# Pwdr-Circuit-0_1_mk1.net
KiCad netlist of a schematic drawn in EAGLE
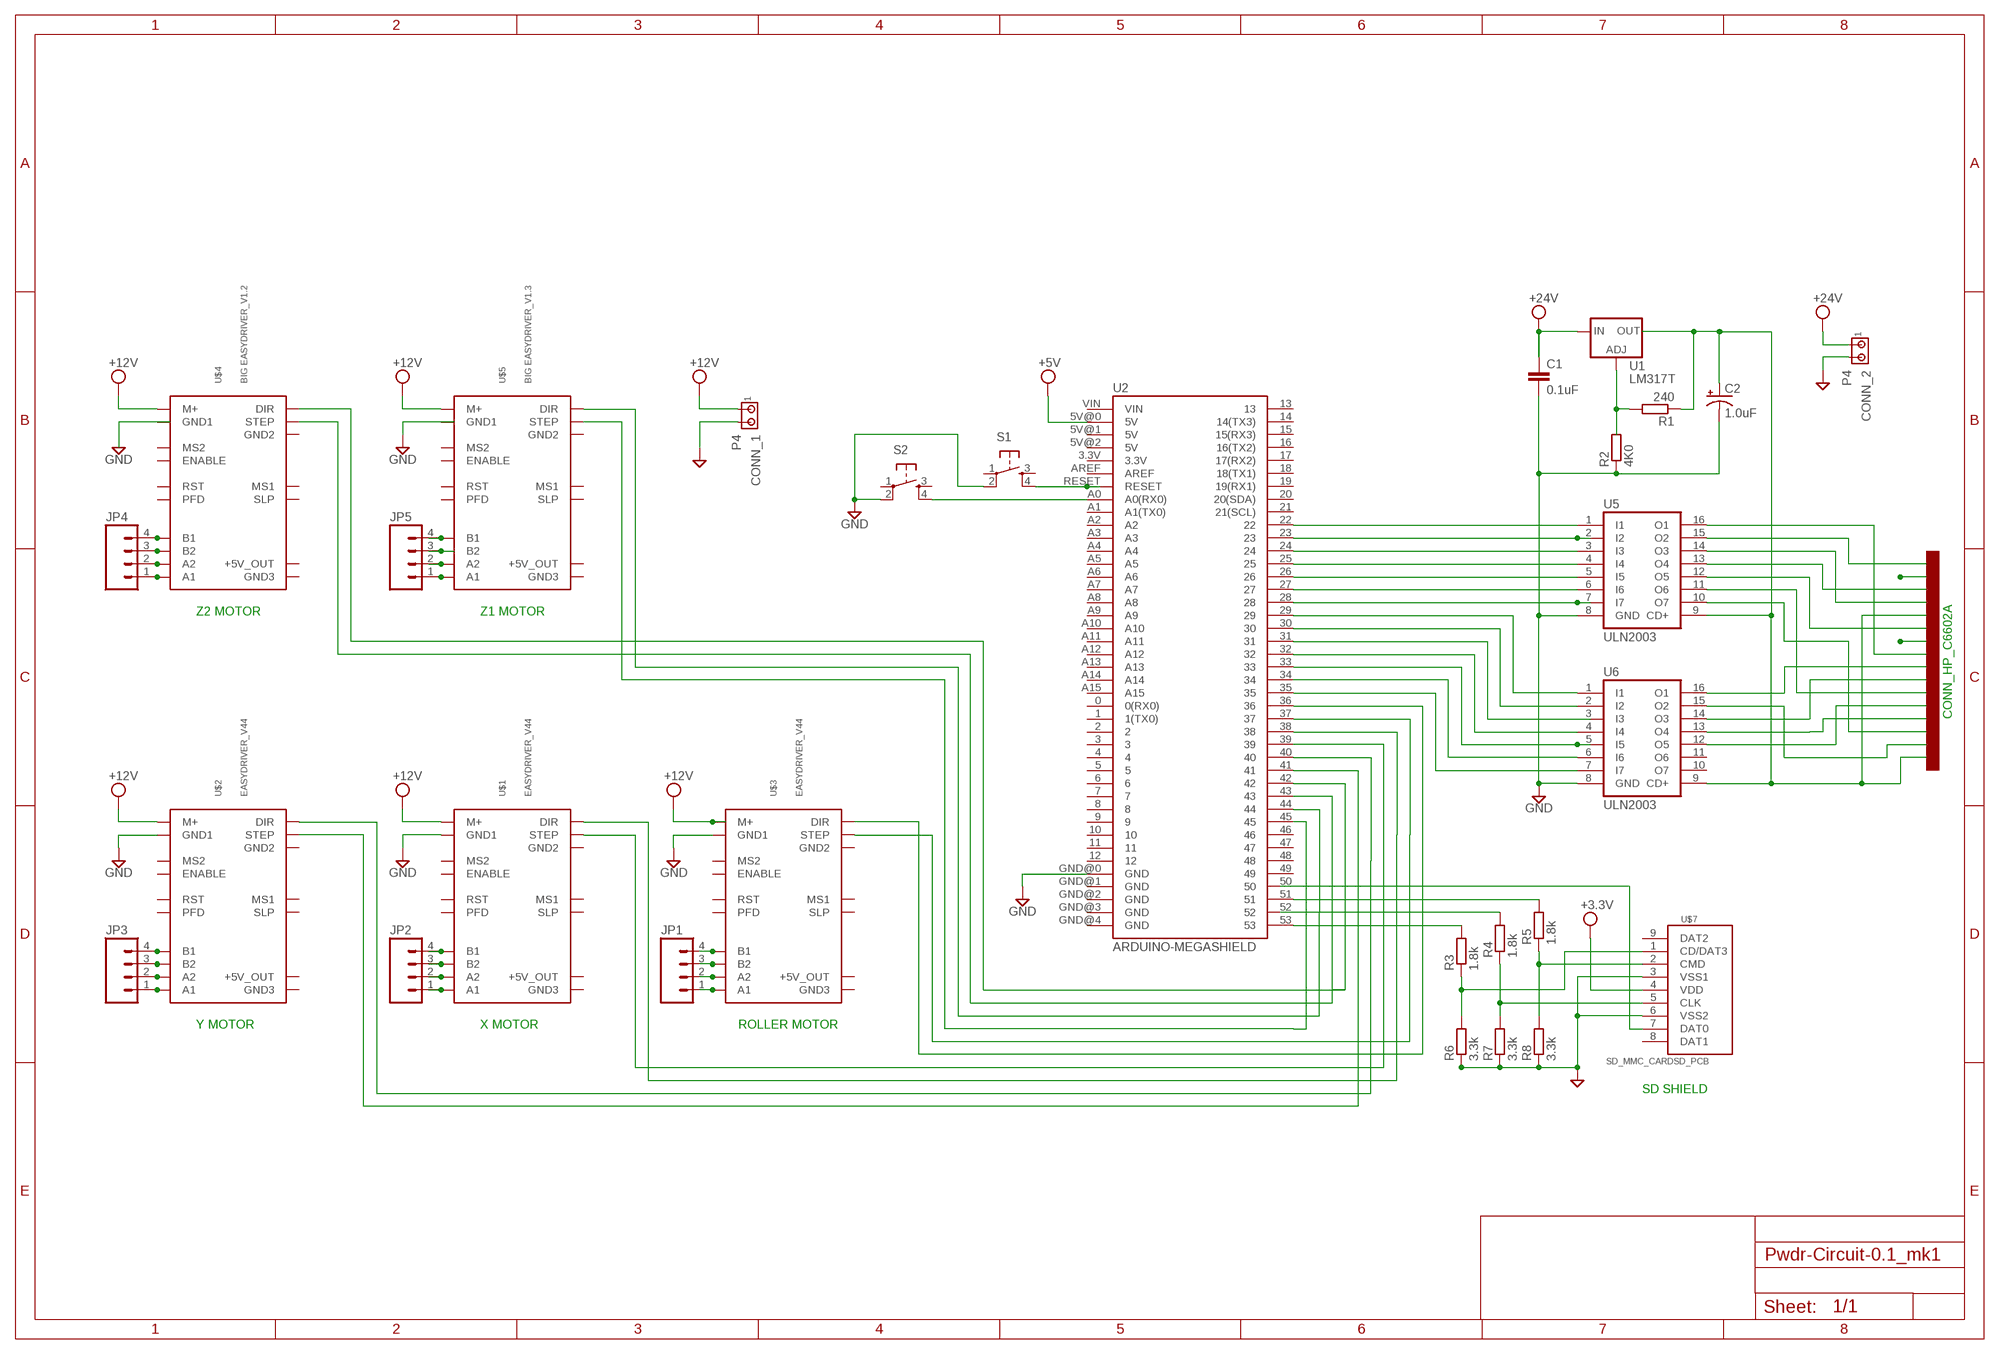
[diagram p0: schematic, sheet 1]

(export (version "E")
  (design (tool "Eeschema 10.0.6"))
  (components
    (comp (ref "C1")
      (value "0.1uF")
      (footprint "eagle-import:C025-024X044")
      (libsource (lib "eagle-import") (part "C-EU025-024X044"))
    )
    (comp (ref "C2")
      (value "1.0uF")
      (footprint "eagle-import:085CS_1AR")
      (libsource (lib "eagle-import") (part "CPOL-US085CS-1AR"))
    )
    (comp (ref "CONN_1")
      (value "P4")
      (footprint "eagle-import:1X2MTA")
      (libsource (lib "eagle-import") (part "MTA02-156"))
    )
    (comp (ref "CONN_2")
      (value "P4")
      (footprint "eagle-import:1X2MTA")
      (libsource (lib "eagle-import") (part "MTA02-156"))
    )
    (comp (ref "JP1")
      (value "M041X04_NO_SILK")
      (footprint "eagle-import:1X04_NO_SILK")
      (libsource (lib "eagle-import") (part "M041X04_NO_SILK"))
    )
    (comp (ref "JP2")
      (value "M041X04_NO_SILK")
      (footprint "eagle-import:1X04_NO_SILK")
      (libsource (lib "eagle-import") (part "M041X04_NO_SILK"))
    )
    (comp (ref "JP3")
      (value "M041X04_NO_SILK")
      (footprint "eagle-import:1X04_NO_SILK")
      (libsource (lib "eagle-import") (part "M041X04_NO_SILK"))
    )
    (comp (ref "JP4")
      (value "M041X04_NO_SILK")
      (footprint "eagle-import:1X04_NO_SILK")
      (libsource (lib "eagle-import") (part "M041X04_NO_SILK"))
    )
    (comp (ref "JP5")
      (value "M041X04_NO_SILK")
      (footprint "eagle-import:1X04_NO_SILK")
      (libsource (lib "eagle-import") (part "M041X04_NO_SILK"))
    )
    (comp (ref "R1")
      (value "240")
      (footprint "eagle-import:0204V")
      (libsource (lib "eagle-import") (part "R-EU_0204/2V"))
    )
    (comp (ref "R2")
      (value "4K0")
      (footprint "eagle-import:0204V")
      (libsource (lib "eagle-import") (part "R-EU_0204/2V"))
    )
    (comp (ref "R3")
      (value "1.8k")
      (footprint "eagle-import:0204V")
      (libsource (lib "eagle-import") (part "R-EU_0204/2V"))
    )
    (comp (ref "R4")
      (value "1.8k")
      (footprint "eagle-import:0204V")
      (libsource (lib "eagle-import") (part "R-EU_0204/2V"))
    )
    (comp (ref "R5")
      (value "1.8k")
      (footprint "eagle-import:0204V")
      (libsource (lib "eagle-import") (part "R-EU_0204/2V"))
    )
    (comp (ref "R6")
      (value "3.3k")
      (footprint "eagle-import:0204V")
      (libsource (lib "eagle-import") (part "R-EU_0204/2V"))
    )
    (comp (ref "R7")
      (value "3.3k")
      (footprint "eagle-import:0204V")
      (libsource (lib "eagle-import") (part "R-EU_0204/2V"))
    )
    (comp (ref "R8")
      (value "3.3k")
      (footprint "eagle-import:0204V")
      (libsource (lib "eagle-import") (part "R-EU_0204/2V"))
    )
    (comp (ref "S1")
      (value "TAC_SWITCHSMD")
      (footprint "eagle-import:TACTILE_SWITCH_SMD")
      (libsource (lib "eagle-import") (part "TAC_SWITCHSMD"))
    )
    (comp (ref "S2")
      (value "TAC_SWITCHSMD")
      (footprint "eagle-import:TACTILE_SWITCH_SMD")
      (libsource (lib "eagle-import") (part "TAC_SWITCHSMD"))
    )
    (comp (ref "U$1")
      (value "EASYDRIVER_V44")
      (footprint "eagle-import:EASYDRIVER_V44")
      (libsource (lib "eagle-import") (part "EASYDRIVER_V44"))
    )
    (comp (ref "U$2")
      (value "EASYDRIVER_V44")
      (footprint "eagle-import:EASYDRIVER_V44")
      (libsource (lib "eagle-import") (part "EASYDRIVER_V44"))
    )
    (comp (ref "U$3")
      (value "EASYDRIVER_V44")
      (footprint "eagle-import:EASYDRIVER_V44")
      (libsource (lib "eagle-import") (part "EASYDRIVER_V44"))
    )
    (comp (ref "U$4")
      (value "BIG EASYDRIVER_V1.2")
      (footprint "eagle-import:EASYDRIVER_V44")
      (libsource (lib "eagle-import") (part "EASYDRIVER_V44"))
    )
    (comp (ref "U$5")
      (value "BIG EASYDRIVER_V1.3")
      (footprint "eagle-import:EASYDRIVER_V44")
      (libsource (lib "eagle-import") (part "EASYDRIVER_V44"))
    )
    (comp (ref "U$7")
      (value "SD_MMC_CARDSD_PCB")
      (footprint "eagle-import:SD-MMC-CARD")
      (libsource (lib "eagle-import") (part "SD_MMC_CARDSD_PCB"))
    )
    (comp (ref "U1")
      (value "LM317T")
      (footprint "eagle-import:317L")
      (libsource (lib "eagle-import") (part "LM317L"))
    )
    (comp (ref "U2")
      (value "ARDUINO-MEGASHIELD")
      (footprint "eagle-import:ARDUINO_MEGA")
      (libsource (lib "eagle-import") (part "ARDUINO-MEGAFULL"))
    )
    (comp (ref "U5")
      (value "ULN2003")
      (footprint "eagle-import:DIL16")
      (libsource (lib "eagle-import") (part "ULN2003AN"))
    )
    (comp (ref "U6")
      (value "ULN2003")
      (footprint "eagle-import:DIL16")
      (libsource (lib "eagle-import") (part "ULN2003AN"))
    )
  )
  (nets
    (net (code "1") (name "+12V") (class "Default")
      (node (ref "C1") (pin "1") (pinfunction "1_1") (pintype "passive"))
      (node (ref "CONN_1") (pin "1") (pinfunction "1_1") (pintype "passive"))
      (node (ref "CONN_2") (pin "1") (pinfunction "1_1") (pintype "passive"))
      (node (ref "U$1") (pin "M+") (pinfunction "M+_M+") (pintype "bidirectional"))
      (node (ref "U$2") (pin "M+") (pinfunction "M+_M+") (pintype "bidirectional"))
      (node (ref "U$3") (pin "M+") (pinfunction "M+_M+") (pintype "bidirectional"))
      (node (ref "U$4") (pin "M+") (pinfunction "M+_M+") (pintype "bidirectional"))
      (node (ref "U$5") (pin "M+") (pinfunction "M+_M+") (pintype "bidirectional"))
      (node (ref "U$7") (pin "4") (pinfunction "VDD_4") (pintype "bidirectional"))
      (node (ref "U1") (pin "3") (pinfunction "IN_3") (pintype "input"))
      (node (ref "U2") (pin "5V@0") (pinfunction "5V_5V@0") (pintype "bidirectional"))
    )
    (net (code "2") (name "AGND") (class "Default")
      (node (ref "C1") (pin "2") (pinfunction "2_2") (pintype "passive"))
      (node (ref "C2") (pin "-") (pinfunction "-_-") (pintype "passive"))
      (node (ref "CONN_1") (pin "2") (pinfunction "2_2") (pintype "passive"))
      (node (ref "CONN_2") (pin "2") (pinfunction "2_2") (pintype "passive"))
      (node (ref "R2") (pin "1") (pinfunction "1_1") (pintype "passive"))
      (node (ref "R6") (pin "1") (pinfunction "1_1") (pintype "passive"))
      (node (ref "R7") (pin "1") (pinfunction "1_1") (pintype "passive"))
      (node (ref "R8") (pin "1") (pinfunction "1_1") (pintype "passive"))
      (node (ref "S1") (pin "2") (pinfunction "2_2") (pintype "passive"))
      (node (ref "S2") (pin "2") (pinfunction "2_2") (pintype "passive"))
      (node (ref "U$1") (pin "GND1") (pinfunction "GND1_GND1") (pintype "bidirectional"))
      (node (ref "U$2") (pin "GND1") (pinfunction "GND1_GND1") (pintype "bidirectional"))
      (node (ref "U$3") (pin "GND1") (pinfunction "GND1_GND1") (pintype "bidirectional"))
      (node (ref "U$4") (pin "GND1") (pinfunction "GND1_GND1") (pintype "bidirectional"))
      (node (ref "U$5") (pin "GND1") (pinfunction "GND1_GND1") (pintype "bidirectional"))
      (node (ref "U$7") (pin "3") (pinfunction "VSS1_3") (pintype "bidirectional"))
      (node (ref "U$7") (pin "6") (pinfunction "VSS2_6") (pintype "bidirectional"))
      (node (ref "U2") (pin "GND@0") (pinfunction "GND_GND@0") (pintype "bidirectional"))
      (node (ref "U5") (pin "8") (pinfunction "GND_8") (pintype "power_in"))
      (node (ref "U6") (pin "8") (pinfunction "GND_8") (pintype "power_in"))
    )
    (net (code "3") (name "Net-(JP1-Pad1)") (class "Default")
      (node (ref "JP1") (pin "1") (pinfunction "1_1") (pintype "passive"))
      (node (ref "U$3") (pin "A1") (pinfunction "A1_A1") (pintype "bidirectional"))
    )
    (net (code "4") (name "Net-(JP1-Pad2)") (class "Default")
      (node (ref "JP1") (pin "2") (pinfunction "2_2") (pintype "passive"))
      (node (ref "U$3") (pin "A2") (pinfunction "A2_A2") (pintype "bidirectional"))
    )
    (net (code "5") (name "Net-(JP1-Pad3)") (class "Default")
      (node (ref "JP1") (pin "3") (pinfunction "3_3") (pintype "passive"))
      (node (ref "U$3") (pin "B2") (pinfunction "B2_B2") (pintype "bidirectional"))
    )
    (net (code "6") (name "Net-(JP1-Pad4)") (class "Default")
      (node (ref "JP1") (pin "4") (pinfunction "4_4") (pintype "passive"))
      (node (ref "U$3") (pin "B1") (pinfunction "B1_B1") (pintype "bidirectional"))
    )
    (net (code "7") (name "Net-(JP2-Pad1)") (class "Default")
      (node (ref "JP2") (pin "1") (pinfunction "1_1") (pintype "passive"))
      (node (ref "U$1") (pin "A1") (pinfunction "A1_A1") (pintype "bidirectional"))
    )
    (net (code "8") (name "Net-(JP2-Pad2)") (class "Default")
      (node (ref "JP2") (pin "2") (pinfunction "2_2") (pintype "passive"))
      (node (ref "U$1") (pin "A2") (pinfunction "A2_A2") (pintype "bidirectional"))
    )
    (net (code "9") (name "Net-(JP2-Pad3)") (class "Default")
      (node (ref "JP2") (pin "3") (pinfunction "3_3") (pintype "passive"))
      (node (ref "U$1") (pin "B2") (pinfunction "B2_B2") (pintype "bidirectional"))
    )
    (net (code "10") (name "Net-(JP2-Pad4)") (class "Default")
      (node (ref "JP2") (pin "4") (pinfunction "4_4") (pintype "passive"))
      (node (ref "U$1") (pin "B1") (pinfunction "B1_B1") (pintype "bidirectional"))
    )
    (net (code "11") (name "Net-(JP3-Pad1)") (class "Default")
      (node (ref "JP3") (pin "1") (pinfunction "1_1") (pintype "passive"))
      (node (ref "U$2") (pin "A1") (pinfunction "A1_A1") (pintype "bidirectional"))
    )
    (net (code "12") (name "Net-(JP3-Pad2)") (class "Default")
      (node (ref "JP3") (pin "2") (pinfunction "2_2") (pintype "passive"))
      (node (ref "U$2") (pin "A2") (pinfunction "A2_A2") (pintype "bidirectional"))
    )
    (net (code "13") (name "Net-(JP3-Pad3)") (class "Default")
      (node (ref "JP3") (pin "3") (pinfunction "3_3") (pintype "passive"))
      (node (ref "U$2") (pin "B2") (pinfunction "B2_B2") (pintype "bidirectional"))
    )
    (net (code "14") (name "Net-(JP3-Pad4)") (class "Default")
      (node (ref "JP3") (pin "4") (pinfunction "4_4") (pintype "passive"))
      (node (ref "U$2") (pin "B1") (pinfunction "B1_B1") (pintype "bidirectional"))
    )
    (net (code "15") (name "Net-(JP4-Pad1)") (class "Default")
      (node (ref "JP4") (pin "1") (pinfunction "1_1") (pintype "passive"))
      (node (ref "U$4") (pin "A1") (pinfunction "A1_A1") (pintype "bidirectional"))
    )
    (net (code "16") (name "Net-(JP4-Pad2)") (class "Default")
      (node (ref "JP4") (pin "2") (pinfunction "2_2") (pintype "passive"))
      (node (ref "U$4") (pin "A2") (pinfunction "A2_A2") (pintype "bidirectional"))
    )
    (net (code "17") (name "Net-(JP4-Pad3)") (class "Default")
      (node (ref "JP4") (pin "3") (pinfunction "3_3") (pintype "passive"))
      (node (ref "U$4") (pin "B2") (pinfunction "B2_B2") (pintype "bidirectional"))
    )
    (net (code "18") (name "Net-(JP4-Pad4)") (class "Default")
      (node (ref "JP4") (pin "4") (pinfunction "4_4") (pintype "passive"))
      (node (ref "U$4") (pin "B1") (pinfunction "B1_B1") (pintype "bidirectional"))
    )
    (net (code "19") (name "Net-(JP5-Pad1)") (class "Default")
      (node (ref "JP5") (pin "1") (pinfunction "1_1") (pintype "passive"))
      (node (ref "U$5") (pin "A1") (pinfunction "A1_A1") (pintype "bidirectional"))
    )
    (net (code "20") (name "Net-(JP5-Pad2)") (class "Default")
      (node (ref "JP5") (pin "2") (pinfunction "2_2") (pintype "passive"))
      (node (ref "U$5") (pin "A2") (pinfunction "A2_A2") (pintype "bidirectional"))
    )
    (net (code "21") (name "Net-(JP5-Pad3)") (class "Default")
      (node (ref "JP5") (pin "3") (pinfunction "3_3") (pintype "passive"))
      (node (ref "U$5") (pin "B2") (pinfunction "B2_B2") (pintype "bidirectional"))
    )
    (net (code "22") (name "Net-(JP5-Pad4)") (class "Default")
      (node (ref "JP5") (pin "4") (pinfunction "4_4") (pintype "passive"))
      (node (ref "U$5") (pin "B1") (pinfunction "B1_B1") (pintype "bidirectional"))
    )
    (net (code "23") (name "Net-(R3-Pad2)") (class "Default")
      (node (ref "R3") (pin "2") (pinfunction "2_2") (pintype "passive"))
      (node (ref "U2") (pin "53") (pinfunction "53_53") (pintype "bidirectional"))
    )
    (net (code "24") (name "Net-(R5-Pad2)") (class "Default")
      (node (ref "R5") (pin "2") (pinfunction "2_2") (pintype "passive"))
      (node (ref "U2") (pin "51") (pinfunction "51_51") (pintype "bidirectional"))
    )
    (net (code "25") (name "Net-(S1-Pad4)") (class "Default")
      (node (ref "S1") (pin "4") (pinfunction "4_4") (pintype "passive"))
      (node (ref "U2") (pin "RESET") (pinfunction "RESET_RESET") (pintype "bidirectional"))
    )
    (net (code "26") (name "Net-(U$1-PadDIR)") (class "Default")
      (node (ref "U$1") (pin "DIR") (pinfunction "DIR_DIR") (pintype "bidirectional"))
      (node (ref "U$2") (pin "DIR") (pinfunction "DIR_DIR") (pintype "bidirectional"))
      (node (ref "U2") (pin "38") (pinfunction "38_38") (pintype "bidirectional"))
      (node (ref "U2") (pin "40") (pinfunction "40_40") (pintype "bidirectional"))
    )
    (net (code "27") (name "Net-(U$1-PadSTEP)") (class "Default")
      (node (ref "U$1") (pin "STEP") (pinfunction "STEP_STEP") (pintype "bidirectional"))
      (node (ref "U2") (pin "39") (pinfunction "39_39") (pintype "bidirectional"))
    )
    (net (code "28") (name "Net-(U$2-PadSTEP)") (class "Default")
      (node (ref "U$2") (pin "STEP") (pinfunction "STEP_STEP") (pintype "bidirectional"))
      (node (ref "U2") (pin "41") (pinfunction "41_41") (pintype "bidirectional"))
    )
    (net (code "29") (name "Net-(U$3-PadDIR)") (class "Default")
      (node (ref "U$3") (pin "DIR") (pinfunction "DIR_DIR") (pintype "bidirectional"))
      (node (ref "U2") (pin "36") (pinfunction "36_36") (pintype "bidirectional"))
    )
    (net (code "30") (name "Net-(U$3-PadSTEP)") (class "Default")
      (node (ref "U$3") (pin "STEP") (pinfunction "STEP_STEP") (pintype "bidirectional"))
      (node (ref "U2") (pin "37") (pinfunction "37_37") (pintype "bidirectional"))
    )
    (net (code "31") (name "Net-(U$4-PadDIR)") (class "Default")
      (node (ref "U$4") (pin "DIR") (pinfunction "DIR_DIR") (pintype "bidirectional"))
      (node (ref "U2") (pin "42") (pinfunction "42_42") (pintype "bidirectional"))
    )
    (net (code "32") (name "Net-(U$4-PadSTEP)") (class "Default")
      (node (ref "U$4") (pin "STEP") (pinfunction "STEP_STEP") (pintype "bidirectional"))
      (node (ref "U2") (pin "43") (pinfunction "43_43") (pintype "bidirectional"))
    )
    (net (code "33") (name "Net-(U$5-PadDIR)") (class "Default")
      (node (ref "U$5") (pin "DIR") (pinfunction "DIR_DIR") (pintype "bidirectional"))
      (node (ref "U2") (pin "44") (pinfunction "44_44") (pintype "bidirectional"))
    )
    (net (code "34") (name "Net-(U$5-PadSTEP)") (class "Default")
      (node (ref "U$5") (pin "STEP") (pinfunction "STEP_STEP") (pintype "bidirectional"))
      (node (ref "U2") (pin "45") (pinfunction "45_45") (pintype "bidirectional"))
    )
    (net (code "35") (name "Net-(U$7-CD{slash}DAT3)") (class "Default")
      (node (ref "R3") (pin "1") (pinfunction "1_1") (pintype "passive"))
      (node (ref "R6") (pin "2") (pinfunction "2_2") (pintype "passive"))
      (node (ref "U$7") (pin "1") (pinfunction "CD/DAT3_1") (pintype "bidirectional"))
    )
    (net (code "36") (name "Net-(U$7-CLK)") (class "Default")
      (node (ref "R4") (pin "1") (pinfunction "1_1") (pintype "passive"))
      (node (ref "R7") (pin "2") (pinfunction "2_2") (pintype "passive"))
      (node (ref "U$7") (pin "5") (pinfunction "CLK_5") (pintype "bidirectional"))
    )
    (net (code "37") (name "Net-(U$7-CMD)") (class "Default")
      (node (ref "R5") (pin "1") (pinfunction "1_1") (pintype "passive"))
      (node (ref "R8") (pin "2") (pinfunction "2_2") (pintype "passive"))
      (node (ref "U$7") (pin "2") (pinfunction "CMD_2") (pintype "bidirectional"))
    )
    (net (code "38") (name "Net-(U1-ADJ)") (class "Default")
      (node (ref "R1") (pin "2") (pinfunction "2_2") (pintype "passive"))
      (node (ref "R2") (pin "2") (pinfunction "2_2") (pintype "passive"))
      (node (ref "U1") (pin "1") (pinfunction "ADJ_1") (pintype "input"))
    )
    (net (code "39") (name "Net-(U1-OUT)") (class "Default")
      (node (ref "C2") (pin "+") (pinfunction "+_+") (pintype "passive"))
      (node (ref "R1") (pin "1") (pinfunction "1_1") (pintype "passive"))
      (node (ref "U1") (pin "2") (pinfunction "OUT_2") (pintype "passive"))
      (node (ref "U5") (pin "9") (pinfunction "CD+_9") (pintype "passive"))
      (node (ref "U6") (pin "9") (pinfunction "CD+_9") (pintype "passive"))
    )
    (net (code "40") (name "Net-(U2-A0(RX0))") (class "Default")
      (node (ref "S2") (pin "4") (pinfunction "4_4") (pintype "passive"))
      (node (ref "U2") (pin "A0") (pinfunction "A0(RX0)_A0") (pintype "bidirectional"))
    )
    (net (code "41") (name "Net-(U5-I1)") (class "Default")
      (node (ref "U2") (pin "22") (pinfunction "22_22") (pintype "bidirectional"))
      (node (ref "U5") (pin "1") (pinfunction "I1_1") (pintype "input"))
    )
    (net (code "42") (name "Net-(U5-I2)") (class "Default")
      (node (ref "U2") (pin "23") (pinfunction "23_23") (pintype "bidirectional"))
      (node (ref "U5") (pin "2") (pinfunction "I2_2") (pintype "input"))
    )
    (net (code "43") (name "Net-(U5-I3)") (class "Default")
      (node (ref "U2") (pin "24") (pinfunction "24_24") (pintype "bidirectional"))
      (node (ref "U5") (pin "3") (pinfunction "I3_3") (pintype "input"))
    )
    (net (code "44") (name "Net-(U5-I4)") (class "Default")
      (node (ref "U2") (pin "25") (pinfunction "25_25") (pintype "bidirectional"))
      (node (ref "U5") (pin "4") (pinfunction "I4_4") (pintype "input"))
    )
    (net (code "45") (name "Net-(U5-I5)") (class "Default")
      (node (ref "U2") (pin "26") (pinfunction "26_26") (pintype "bidirectional"))
      (node (ref "U5") (pin "5") (pinfunction "I5_5") (pintype "input"))
    )
    (net (code "46") (name "Net-(U5-I6)") (class "Default")
      (node (ref "U2") (pin "27") (pinfunction "27_27") (pintype "bidirectional"))
      (node (ref "U5") (pin "6") (pinfunction "I6_6") (pintype "input"))
    )
    (net (code "47") (name "Net-(U5-I7)") (class "Default")
      (node (ref "U2") (pin "28") (pinfunction "28_28") (pintype "bidirectional"))
      (node (ref "U5") (pin "7") (pinfunction "I7_7") (pintype "input"))
    )
    (net (code "48") (name "Net-(U6-I1)") (class "Default")
      (node (ref "U2") (pin "29") (pinfunction "29_29") (pintype "bidirectional"))
      (node (ref "U6") (pin "1") (pinfunction "I1_1") (pintype "input"))
    )
    (net (code "49") (name "Net-(U6-I2)") (class "Default")
      (node (ref "U2") (pin "30") (pinfunction "30_30") (pintype "bidirectional"))
      (node (ref "U6") (pin "2") (pinfunction "I2_2") (pintype "input"))
    )
    (net (code "50") (name "Net-(U6-I3)") (class "Default")
      (node (ref "U2") (pin "31") (pinfunction "31_31") (pintype "bidirectional"))
      (node (ref "U6") (pin "3") (pinfunction "I3_3") (pintype "input"))
    )
    (net (code "51") (name "Net-(U6-I4)") (class "Default")
      (node (ref "U2") (pin "32") (pinfunction "32_32") (pintype "bidirectional"))
      (node (ref "U6") (pin "4") (pinfunction "I4_4") (pintype "input"))
    )
    (net (code "52") (name "Net-(U6-I5)") (class "Default")
      (node (ref "U2") (pin "33") (pinfunction "33_33") (pintype "bidirectional"))
      (node (ref "U6") (pin "5") (pinfunction "I5_5") (pintype "input"))
    )
    (net (code "53") (name "Net-(U6-I6)") (class "Default")
      (node (ref "U2") (pin "34") (pinfunction "34_34") (pintype "bidirectional"))
      (node (ref "U6") (pin "6") (pinfunction "I6_6") (pintype "input"))
    )
    (net (code "54") (name "Net-(U6-I7)") (class "Default")
      (node (ref "U2") (pin "35") (pinfunction "35_35") (pintype "bidirectional"))
      (node (ref "U6") (pin "7") (pinfunction "I7_7") (pintype "input"))
    )
    (net (code "55") (name "unconnected-(R4-Pad2)") (class "Default")
      (node (ref "R4") (pin "2") (pinfunction "2_2") (pintype "passive"))
    )
    (net (code "56") (name "unconnected-(S1-Pad1)") (class "Default")
      (node (ref "S1") (pin "1") (pinfunction "1_1") (pintype "passive"))
    )
    (net (code "57") (name "unconnected-(S1-Pad3)") (class "Default")
      (node (ref "S1") (pin "3") (pinfunction "3_3") (pintype "passive"))
    )
    (net (code "58") (name "unconnected-(S2-Pad1)") (class "Default")
      (node (ref "S2") (pin "1") (pinfunction "1_1") (pintype "passive"))
    )
    (net (code "59") (name "unconnected-(S2-Pad3)") (class "Default")
      (node (ref "S2") (pin "3") (pinfunction "3_3") (pintype "passive"))
    )
    (net (code "60") (name "unconnected-(U$1-+5V_OUT-PadP$11)") (class "Default")
      (node (ref "U$1") (pin "P$11") (pinfunction "+5V_OUT_P$11") (pintype "bidirectional"))
    )
    (net (code "61") (name "unconnected-(U$1-PadENABLE)") (class "Default")
      (node (ref "U$1") (pin "ENABLE") (pinfunction "ENABLE_ENABLE") (pintype "bidirectional"))
    )
    (net (code "62") (name "unconnected-(U$1-PadGND2)") (class "Default")
      (node (ref "U$1") (pin "GND2") (pinfunction "GND2_GND2") (pintype "bidirectional"))
    )
    (net (code "63") (name "unconnected-(U$1-PadGND3)") (class "Default")
      (node (ref "U$1") (pin "GND3") (pinfunction "GND3_GND3") (pintype "bidirectional"))
    )
    (net (code "64") (name "unconnected-(U$1-PadMS1)") (class "Default")
      (node (ref "U$1") (pin "MS1") (pinfunction "MS1_MS1") (pintype "bidirectional"))
    )
    (net (code "65") (name "unconnected-(U$1-PadMS2)") (class "Default")
      (node (ref "U$1") (pin "MS2") (pinfunction "MS2_MS2") (pintype "bidirectional"))
    )
    (net (code "66") (name "unconnected-(U$1-PadPFD)") (class "Default")
      (node (ref "U$1") (pin "PFD") (pinfunction "PFD_PFD") (pintype "bidirectional"))
    )
    (net (code "67") (name "unconnected-(U$1-PadRST)") (class "Default")
      (node (ref "U$1") (pin "RST") (pinfunction "RST_RST") (pintype "bidirectional"))
    )
    (net (code "68") (name "unconnected-(U$1-SLP-PadSLEEP)") (class "Default")
      (node (ref "U$1") (pin "SLEEP") (pinfunction "SLP_SLEEP") (pintype "bidirectional"))
    )
    (net (code "69") (name "unconnected-(U$2-+5V_OUT-PadP$11)") (class "Default")
      (node (ref "U$2") (pin "P$11") (pinfunction "+5V_OUT_P$11") (pintype "bidirectional"))
    )
    (net (code "70") (name "unconnected-(U$2-PadENABLE)") (class "Default")
      (node (ref "U$2") (pin "ENABLE") (pinfunction "ENABLE_ENABLE") (pintype "bidirectional"))
    )
    (net (code "71") (name "unconnected-(U$2-PadGND2)") (class "Default")
      (node (ref "U$2") (pin "GND2") (pinfunction "GND2_GND2") (pintype "bidirectional"))
    )
    (net (code "72") (name "unconnected-(U$2-PadGND3)") (class "Default")
      (node (ref "U$2") (pin "GND3") (pinfunction "GND3_GND3") (pintype "bidirectional"))
    )
    (net (code "73") (name "unconnected-(U$2-PadMS1)") (class "Default")
      (node (ref "U$2") (pin "MS1") (pinfunction "MS1_MS1") (pintype "bidirectional"))
    )
    (net (code "74") (name "unconnected-(U$2-PadMS2)") (class "Default")
      (node (ref "U$2") (pin "MS2") (pinfunction "MS2_MS2") (pintype "bidirectional"))
    )
    (net (code "75") (name "unconnected-(U$2-PadPFD)") (class "Default")
      (node (ref "U$2") (pin "PFD") (pinfunction "PFD_PFD") (pintype "bidirectional"))
    )
    (net (code "76") (name "unconnected-(U$2-PadRST)") (class "Default")
      (node (ref "U$2") (pin "RST") (pinfunction "RST_RST") (pintype "bidirectional"))
    )
    (net (code "77") (name "unconnected-(U$2-SLP-PadSLEEP)") (class "Default")
      (node (ref "U$2") (pin "SLEEP") (pinfunction "SLP_SLEEP") (pintype "bidirectional"))
    )
    (net (code "78") (name "unconnected-(U$3-+5V_OUT-PadP$11)") (class "Default")
      (node (ref "U$3") (pin "P$11") (pinfunction "+5V_OUT_P$11") (pintype "bidirectional"))
    )
    (net (code "79") (name "unconnected-(U$3-PadENABLE)") (class "Default")
      (node (ref "U$3") (pin "ENABLE") (pinfunction "ENABLE_ENABLE") (pintype "bidirectional"))
    )
    (net (code "80") (name "unconnected-(U$3-PadGND2)") (class "Default")
      (node (ref "U$3") (pin "GND2") (pinfunction "GND2_GND2") (pintype "bidirectional"))
    )
    (net (code "81") (name "unconnected-(U$3-PadGND3)") (class "Default")
      (node (ref "U$3") (pin "GND3") (pinfunction "GND3_GND3") (pintype "bidirectional"))
    )
    (net (code "82") (name "unconnected-(U$3-PadMS1)") (class "Default")
      (node (ref "U$3") (pin "MS1") (pinfunction "MS1_MS1") (pintype "bidirectional"))
    )
    (net (code "83") (name "unconnected-(U$3-PadMS2)") (class "Default")
      (node (ref "U$3") (pin "MS2") (pinfunction "MS2_MS2") (pintype "bidirectional"))
    )
    (net (code "84") (name "unconnected-(U$3-PadPFD)") (class "Default")
      (node (ref "U$3") (pin "PFD") (pinfunction "PFD_PFD") (pintype "bidirectional"))
    )
    (net (code "85") (name "unconnected-(U$3-PadRST)") (class "Default")
      (node (ref "U$3") (pin "RST") (pinfunction "RST_RST") (pintype "bidirectional"))
    )
    (net (code "86") (name "unconnected-(U$3-SLP-PadSLEEP)") (class "Default")
      (node (ref "U$3") (pin "SLEEP") (pinfunction "SLP_SLEEP") (pintype "bidirectional"))
    )
    (net (code "87") (name "unconnected-(U$4-+5V_OUT-PadP$11)") (class "Default")
      (node (ref "U$4") (pin "P$11") (pinfunction "+5V_OUT_P$11") (pintype "bidirectional"))
    )
    (net (code "88") (name "unconnected-(U$4-PadENABLE)") (class "Default")
      (node (ref "U$4") (pin "ENABLE") (pinfunction "ENABLE_ENABLE") (pintype "bidirectional"))
    )
    (net (code "89") (name "unconnected-(U$4-PadGND2)") (class "Default")
      (node (ref "U$4") (pin "GND2") (pinfunction "GND2_GND2") (pintype "bidirectional"))
    )
    (net (code "90") (name "unconnected-(U$4-PadGND3)") (class "Default")
      (node (ref "U$4") (pin "GND3") (pinfunction "GND3_GND3") (pintype "bidirectional"))
    )
    (net (code "91") (name "unconnected-(U$4-PadMS1)") (class "Default")
      (node (ref "U$4") (pin "MS1") (pinfunction "MS1_MS1") (pintype "bidirectional"))
    )
    (net (code "92") (name "unconnected-(U$4-PadMS2)") (class "Default")
      (node (ref "U$4") (pin "MS2") (pinfunction "MS2_MS2") (pintype "bidirectional"))
    )
    (net (code "93") (name "unconnected-(U$4-PadPFD)") (class "Default")
      (node (ref "U$4") (pin "PFD") (pinfunction "PFD_PFD") (pintype "bidirectional"))
    )
    (net (code "94") (name "unconnected-(U$4-PadRST)") (class "Default")
      (node (ref "U$4") (pin "RST") (pinfunction "RST_RST") (pintype "bidirectional"))
    )
    (net (code "95") (name "unconnected-(U$4-SLP-PadSLEEP)") (class "Default")
      (node (ref "U$4") (pin "SLEEP") (pinfunction "SLP_SLEEP") (pintype "bidirectional"))
    )
    (net (code "96") (name "unconnected-(U$5-+5V_OUT-PadP$11)") (class "Default")
      (node (ref "U$5") (pin "P$11") (pinfunction "+5V_OUT_P$11") (pintype "bidirectional"))
    )
    (net (code "97") (name "unconnected-(U$5-PadENABLE)") (class "Default")
      (node (ref "U$5") (pin "ENABLE") (pinfunction "ENABLE_ENABLE") (pintype "bidirectional"))
    )
    (net (code "98") (name "unconnected-(U$5-PadGND2)") (class "Default")
      (node (ref "U$5") (pin "GND2") (pinfunction "GND2_GND2") (pintype "bidirectional"))
    )
    (net (code "99") (name "unconnected-(U$5-PadGND3)") (class "Default")
      (node (ref "U$5") (pin "GND3") (pinfunction "GND3_GND3") (pintype "bidirectional"))
    )
    (net (code "100") (name "unconnected-(U$5-PadMS1)") (class "Default")
      (node (ref "U$5") (pin "MS1") (pinfunction "MS1_MS1") (pintype "bidirectional"))
    )
    (net (code "101") (name "unconnected-(U$5-PadMS2)") (class "Default")
      (node (ref "U$5") (pin "MS2") (pinfunction "MS2_MS2") (pintype "bidirectional"))
    )
    (net (code "102") (name "unconnected-(U$5-PadPFD)") (class "Default")
      (node (ref "U$5") (pin "PFD") (pinfunction "PFD_PFD") (pintype "bidirectional"))
    )
    (net (code "103") (name "unconnected-(U$5-PadRST)") (class "Default")
      (node (ref "U$5") (pin "RST") (pinfunction "RST_RST") (pintype "bidirectional"))
    )
    (net (code "104") (name "unconnected-(U$5-SLP-PadSLEEP)") (class "Default")
      (node (ref "U$5") (pin "SLEEP") (pinfunction "SLP_SLEEP") (pintype "bidirectional"))
    )
    (net (code "105") (name "unconnected-(U$7-DAT0-Pad7)") (class "Default")
      (node (ref "U$7") (pin "7") (pinfunction "DAT0_7") (pintype "bidirectional"))
    )
    (net (code "106") (name "unconnected-(U$7-DAT1-Pad8)") (class "Default")
      (node (ref "U$7") (pin "8") (pinfunction "DAT1_8") (pintype "bidirectional"))
    )
    (net (code "107") (name "unconnected-(U$7-DAT2-Pad9)") (class "Default")
      (node (ref "U$7") (pin "9") (pinfunction "DAT2_9") (pintype "bidirectional"))
    )
    (net (code "108") (name "unconnected-(U2-0(RX0)-Pad0)") (class "Default")
      (node (ref "U2") (pin "0") (pinfunction "0(RX0)_0") (pintype "bidirectional"))
    )
    (net (code "109") (name "unconnected-(U2-1(TX0)-Pad1)") (class "Default")
      (node (ref "U2") (pin "1") (pinfunction "1(TX0)_1") (pintype "bidirectional"))
    )
    (net (code "110") (name "unconnected-(U2-5V-Pad5V@1)") (class "Default")
      (node (ref "U2") (pin "5V@1") (pinfunction "5V_5V@1") (pintype "bidirectional"))
    )
    (net (code "111") (name "unconnected-(U2-5V-Pad5V@2)") (class "Default")
      (node (ref "U2") (pin "5V@2") (pinfunction "5V_5V@2") (pintype "bidirectional"))
    )
    (net (code "112") (name "unconnected-(U2-14(TX3)-Pad14)") (class "Default")
      (node (ref "U2") (pin "14") (pinfunction "14(TX3)_14") (pintype "bidirectional"))
    )
    (net (code "113") (name "unconnected-(U2-15(RX3)-Pad15)") (class "Default")
      (node (ref "U2") (pin "15") (pinfunction "15(RX3)_15") (pintype "bidirectional"))
    )
    (net (code "114") (name "unconnected-(U2-16(TX2)-Pad16)") (class "Default")
      (node (ref "U2") (pin "16") (pinfunction "16(TX2)_16") (pintype "bidirectional"))
    )
    (net (code "115") (name "unconnected-(U2-17(RX2)-Pad17)") (class "Default")
      (node (ref "U2") (pin "17") (pinfunction "17(RX2)_17") (pintype "bidirectional"))
    )
    (net (code "116") (name "unconnected-(U2-18(TX1)-Pad18)") (class "Default")
      (node (ref "U2") (pin "18") (pinfunction "18(TX1)_18") (pintype "bidirectional"))
    )
    (net (code "117") (name "unconnected-(U2-19(RX1)-Pad19)") (class "Default")
      (node (ref "U2") (pin "19") (pinfunction "19(RX1)_19") (pintype "bidirectional"))
    )
    (net (code "118") (name "unconnected-(U2-20(SDA)-Pad20)") (class "Default")
      (node (ref "U2") (pin "20") (pinfunction "20(SDA)_20") (pintype "bidirectional"))
    )
    (net (code "119") (name "unconnected-(U2-21(SCL)-Pad21)") (class "Default")
      (node (ref "U2") (pin "21") (pinfunction "21(SCL)_21") (pintype "bidirectional"))
    )
    (net (code "120") (name "unconnected-(U2-A1(TX0)-PadA1)") (class "Default")
      (node (ref "U2") (pin "A1") (pinfunction "A1(TX0)_A1") (pintype "bidirectional"))
    )
    (net (code "121") (name "unconnected-(U2-GND-PadGND@1)") (class "Default")
      (node (ref "U2") (pin "GND@1") (pinfunction "GND_GND@1") (pintype "bidirectional"))
    )
    (net (code "122") (name "unconnected-(U2-GND-PadGND@2)") (class "Default")
      (node (ref "U2") (pin "GND@2") (pinfunction "GND_GND@2") (pintype "bidirectional"))
    )
    (net (code "123") (name "unconnected-(U2-GND-PadGND@3)") (class "Default")
      (node (ref "U2") (pin "GND@3") (pinfunction "GND_GND@3") (pintype "bidirectional"))
    )
    (net (code "124") (name "unconnected-(U2-GND-PadGND@4)") (class "Default")
      (node (ref "U2") (pin "GND@4") (pinfunction "GND_GND@4") (pintype "bidirectional"))
    )
    (net (code "125") (name "unconnected-(U2-Pad2)") (class "Default")
      (node (ref "U2") (pin "2") (pinfunction "2_2") (pintype "bidirectional"))
    )
    (net (code "126") (name "unconnected-(U2-Pad3)") (class "Default")
      (node (ref "U2") (pin "3") (pinfunction "3_3") (pintype "bidirectional"))
    )
    (net (code "127") (name "unconnected-(U2-Pad3.3V)") (class "Default")
      (node (ref "U2") (pin "3.3V") (pinfunction "3.3V_3.3V") (pintype "bidirectional"))
    )
    (net (code "128") (name "unconnected-(U2-Pad4)") (class "Default")
      (node (ref "U2") (pin "4") (pinfunction "4_4") (pintype "bidirectional"))
    )
    (net (code "129") (name "unconnected-(U2-Pad5)") (class "Default")
      (node (ref "U2") (pin "5") (pinfunction "5_5") (pintype "bidirectional"))
    )
    (net (code "130") (name "unconnected-(U2-Pad6)") (class "Default")
      (node (ref "U2") (pin "6") (pinfunction "6_6") (pintype "bidirectional"))
    )
    (net (code "131") (name "unconnected-(U2-Pad7)") (class "Default")
      (node (ref "U2") (pin "7") (pinfunction "7_7") (pintype "bidirectional"))
    )
    (net (code "132") (name "unconnected-(U2-Pad8)") (class "Default")
      (node (ref "U2") (pin "8") (pinfunction "8_8") (pintype "bidirectional"))
    )
    (net (code "133") (name "unconnected-(U2-Pad9)") (class "Default")
      (node (ref "U2") (pin "9") (pinfunction "9_9") (pintype "bidirectional"))
    )
    (net (code "134") (name "unconnected-(U2-Pad10)") (class "Default")
      (node (ref "U2") (pin "10") (pinfunction "10_10") (pintype "bidirectional"))
    )
    (net (code "135") (name "unconnected-(U2-Pad11)") (class "Default")
      (node (ref "U2") (pin "11") (pinfunction "11_11") (pintype "bidirectional"))
    )
    (net (code "136") (name "unconnected-(U2-Pad12)") (class "Default")
      (node (ref "U2") (pin "12") (pinfunction "12_12") (pintype "bidirectional"))
    )
    (net (code "137") (name "unconnected-(U2-Pad13)") (class "Default")
      (node (ref "U2") (pin "13") (pinfunction "13_13") (pintype "bidirectional"))
    )
    (net (code "138") (name "unconnected-(U2-Pad46)") (class "Default")
      (node (ref "U2") (pin "46") (pinfunction "46_46") (pintype "bidirectional"))
    )
    (net (code "139") (name "unconnected-(U2-Pad47)") (class "Default")
      (node (ref "U2") (pin "47") (pinfunction "47_47") (pintype "bidirectional"))
    )
    (net (code "140") (name "unconnected-(U2-Pad48)") (class "Default")
      (node (ref "U2") (pin "48") (pinfunction "48_48") (pintype "bidirectional"))
    )
    (net (code "141") (name "unconnected-(U2-Pad49)") (class "Default")
      (node (ref "U2") (pin "49") (pinfunction "49_49") (pintype "bidirectional"))
    )
    (net (code "142") (name "unconnected-(U2-Pad50)") (class "Default")
      (node (ref "U2") (pin "50") (pinfunction "50_50") (pintype "bidirectional"))
    )
    (net (code "143") (name "unconnected-(U2-Pad52)") (class "Default")
      (node (ref "U2") (pin "52") (pinfunction "52_52") (pintype "bidirectional"))
    )
    (net (code "144") (name "unconnected-(U2-PadA2)") (class "Default")
      (node (ref "U2") (pin "A2") (pinfunction "A2_A2") (pintype "bidirectional"))
    )
    (net (code "145") (name "unconnected-(U2-PadA3)") (class "Default")
      (node (ref "U2") (pin "A3") (pinfunction "A3_A3") (pintype "bidirectional"))
    )
    (net (code "146") (name "unconnected-(U2-PadA4)") (class "Default")
      (node (ref "U2") (pin "A4") (pinfunction "A4_A4") (pintype "bidirectional"))
    )
    (net (code "147") (name "unconnected-(U2-PadA5)") (class "Default")
      (node (ref "U2") (pin "A5") (pinfunction "A5_A5") (pintype "bidirectional"))
    )
    (net (code "148") (name "unconnected-(U2-PadA6)") (class "Default")
      (node (ref "U2") (pin "A6") (pinfunction "A6_A6") (pintype "bidirectional"))
    )
    (net (code "149") (name "unconnected-(U2-PadA7)") (class "Default")
      (node (ref "U2") (pin "A7") (pinfunction "A7_A7") (pintype "bidirectional"))
    )
    (net (code "150") (name "unconnected-(U2-PadA8)") (class "Default")
      (node (ref "U2") (pin "A8") (pinfunction "A8_A8") (pintype "bidirectional"))
    )
    (net (code "151") (name "unconnected-(U2-PadA9)") (class "Default")
      (node (ref "U2") (pin "A9") (pinfunction "A9_A9") (pintype "bidirectional"))
    )
    (net (code "152") (name "unconnected-(U2-PadA10)") (class "Default")
      (node (ref "U2") (pin "A10") (pinfunction "A10_A10") (pintype "bidirectional"))
    )
    (net (code "153") (name "unconnected-(U2-PadA11)") (class "Default")
      (node (ref "U2") (pin "A11") (pinfunction "A11_A11") (pintype "bidirectional"))
    )
    (net (code "154") (name "unconnected-(U2-PadA12)") (class "Default")
      (node (ref "U2") (pin "A12") (pinfunction "A12_A12") (pintype "bidirectional"))
    )
    (net (code "155") (name "unconnected-(U2-PadA13)") (class "Default")
      (node (ref "U2") (pin "A13") (pinfunction "A13_A13") (pintype "bidirectional"))
    )
    (net (code "156") (name "unconnected-(U2-PadA14)") (class "Default")
      (node (ref "U2") (pin "A14") (pinfunction "A14_A14") (pintype "bidirectional"))
    )
    (net (code "157") (name "unconnected-(U2-PadA15)") (class "Default")
      (node (ref "U2") (pin "A15") (pinfunction "A15_A15") (pintype "bidirectional"))
    )
    (net (code "158") (name "unconnected-(U2-PadAREF)") (class "Default")
      (node (ref "U2") (pin "AREF") (pinfunction "AREF_AREF") (pintype "bidirectional"))
    )
    (net (code "159") (name "unconnected-(U2-PadVIN)") (class "Default")
      (node (ref "U2") (pin "VIN") (pinfunction "VIN_VIN") (pintype "bidirectional"))
    )
    (net (code "160") (name "unconnected-(U5-O1-Pad16)") (class "Default")
      (node (ref "U5") (pin "16") (pinfunction "O1_16") (pintype "open_collector"))
    )
    (net (code "161") (name "unconnected-(U5-O2-Pad15)") (class "Default")
      (node (ref "U5") (pin "15") (pinfunction "O2_15") (pintype "open_collector"))
    )
    (net (code "162") (name "unconnected-(U5-O3-Pad14)") (class "Default")
      (node (ref "U5") (pin "14") (pinfunction "O3_14") (pintype "open_collector"))
    )
    (net (code "163") (name "unconnected-(U5-O4-Pad13)") (class "Default")
      (node (ref "U5") (pin "13") (pinfunction "O4_13") (pintype "open_collector"))
    )
    (net (code "164") (name "unconnected-(U5-O5-Pad12)") (class "Default")
      (node (ref "U5") (pin "12") (pinfunction "O5_12") (pintype "open_collector"))
    )
    (net (code "165") (name "unconnected-(U5-O6-Pad11)") (class "Default")
      (node (ref "U5") (pin "11") (pinfunction "O6_11") (pintype "open_collector"))
    )
    (net (code "166") (name "unconnected-(U5-O7-Pad10)") (class "Default")
      (node (ref "U5") (pin "10") (pinfunction "O7_10") (pintype "open_collector"))
    )
    (net (code "167") (name "unconnected-(U6-O1-Pad16)") (class "Default")
      (node (ref "U6") (pin "16") (pinfunction "O1_16") (pintype "open_collector"))
    )
    (net (code "168") (name "unconnected-(U6-O2-Pad15)") (class "Default")
      (node (ref "U6") (pin "15") (pinfunction "O2_15") (pintype "open_collector"))
    )
    (net (code "169") (name "unconnected-(U6-O3-Pad14)") (class "Default")
      (node (ref "U6") (pin "14") (pinfunction "O3_14") (pintype "open_collector"))
    )
    (net (code "170") (name "unconnected-(U6-O4-Pad13)") (class "Default")
      (node (ref "U6") (pin "13") (pinfunction "O4_13") (pintype "open_collector"))
    )
    (net (code "171") (name "unconnected-(U6-O5-Pad12)") (class "Default")
      (node (ref "U6") (pin "12") (pinfunction "O5_12") (pintype "open_collector"))
    )
    (net (code "172") (name "unconnected-(U6-O6-Pad11)") (class "Default")
      (node (ref "U6") (pin "11") (pinfunction "O6_11") (pintype "open_collector"))
    )
    (net (code "173") (name "unconnected-(U6-O7-Pad10)") (class "Default")
      (node (ref "U6") (pin "10") (pinfunction "O7_10") (pintype "open_collector"))
    )
  )
)
